# fat-mic-array.net
KiCad netlist of a schematic drawn in EAGLE
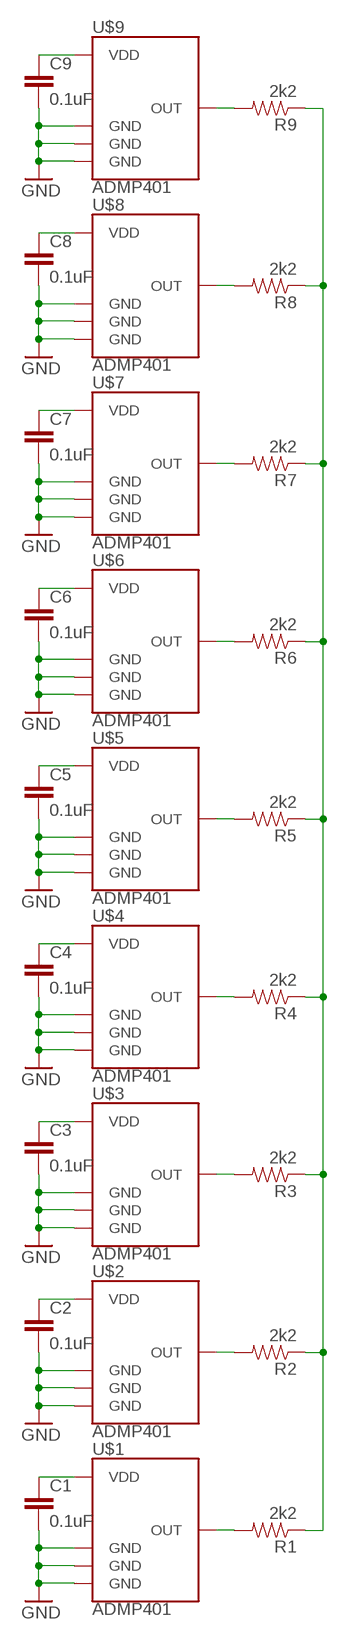
[diagram p0: schematic, sheet 1]

(export (version "E")
  (design (tool "Eeschema 10.0.6"))
  (components
    (comp (ref "C1")
      (value "0.1uF")
      (footprint "eagle-import:0402-CAP")
      (libsource (lib "eagle-import") (part "0.1UF-16V(+-10%)(0402)"))
    )
    (comp (ref "C2")
      (value "0.1uF")
      (footprint "eagle-import:0402-CAP")
      (libsource (lib "eagle-import") (part "0.1UF-16V(+-10%)(0402)"))
    )
    (comp (ref "C3")
      (value "0.1uF")
      (footprint "eagle-import:0402-CAP")
      (libsource (lib "eagle-import") (part "0.1UF-16V(+-10%)(0402)"))
    )
    (comp (ref "C4")
      (value "0.1uF")
      (footprint "eagle-import:0402-CAP")
      (libsource (lib "eagle-import") (part "0.1UF-16V(+-10%)(0402)"))
    )
    (comp (ref "C5")
      (value "0.1uF")
      (footprint "eagle-import:0402-CAP")
      (libsource (lib "eagle-import") (part "0.1UF-16V(+-10%)(0402)"))
    )
    (comp (ref "C6")
      (value "0.1uF")
      (footprint "eagle-import:0402-CAP")
      (libsource (lib "eagle-import") (part "0.1UF-16V(+-10%)(0402)"))
    )
    (comp (ref "C7")
      (value "0.1uF")
      (footprint "eagle-import:0402-CAP")
      (libsource (lib "eagle-import") (part "0.1UF-16V(+-10%)(0402)"))
    )
    (comp (ref "C8")
      (value "0.1uF")
      (footprint "eagle-import:0402-CAP")
      (libsource (lib "eagle-import") (part "0.1UF-16V(+-10%)(0402)"))
    )
    (comp (ref "C9")
      (value "0.1uF")
      (footprint "eagle-import:0402-CAP")
      (libsource (lib "eagle-import") (part "0.1UF-16V(+-10%)(0402)"))
    )
    (comp (ref "R1")
      (value "2k2")
      (footprint "eagle-import:0402-RES")
      (libsource (lib "eagle-import") (part "RESISTOR0402-RES"))
    )
    (comp (ref "R2")
      (value "2k2")
      (footprint "eagle-import:0402-RES")
      (libsource (lib "eagle-import") (part "RESISTOR0402-RES"))
    )
    (comp (ref "R3")
      (value "2k2")
      (footprint "eagle-import:0402-RES")
      (libsource (lib "eagle-import") (part "RESISTOR0402-RES"))
    )
    (comp (ref "R4")
      (value "2k2")
      (footprint "eagle-import:0402-RES")
      (libsource (lib "eagle-import") (part "RESISTOR0402-RES"))
    )
    (comp (ref "R5")
      (value "2k2")
      (footprint "eagle-import:0402-RES")
      (libsource (lib "eagle-import") (part "RESISTOR0402-RES"))
    )
    (comp (ref "R6")
      (value "2k2")
      (footprint "eagle-import:0402-RES")
      (libsource (lib "eagle-import") (part "RESISTOR0402-RES"))
    )
    (comp (ref "R7")
      (value "2k2")
      (footprint "eagle-import:0402-RES")
      (libsource (lib "eagle-import") (part "RESISTOR0402-RES"))
    )
    (comp (ref "R8")
      (value "2k2")
      (footprint "eagle-import:0402-RES")
      (libsource (lib "eagle-import") (part "RESISTOR0402-RES"))
    )
    (comp (ref "R9")
      (value "2k2")
      (footprint "eagle-import:0402-RES")
      (libsource (lib "eagle-import") (part "RESISTOR0402-RES"))
    )
    (comp (ref "U$1")
      (value "ADMP401")
      (footprint "eagle-import:ADMP401")
      (libsource (lib "eagle-import") (part "ADMP401"))
    )
    (comp (ref "U$2")
      (value "ADMP401")
      (footprint "eagle-import:ADMP401")
      (libsource (lib "eagle-import") (part "ADMP401"))
    )
    (comp (ref "U$3")
      (value "ADMP401")
      (footprint "eagle-import:ADMP401")
      (libsource (lib "eagle-import") (part "ADMP401"))
    )
    (comp (ref "U$4")
      (value "ADMP401")
      (footprint "eagle-import:ADMP401")
      (libsource (lib "eagle-import") (part "ADMP401"))
    )
    (comp (ref "U$5")
      (value "ADMP401")
      (footprint "eagle-import:ADMP401")
      (libsource (lib "eagle-import") (part "ADMP401"))
    )
    (comp (ref "U$6")
      (value "ADMP401")
      (footprint "eagle-import:ADMP401")
      (libsource (lib "eagle-import") (part "ADMP401"))
    )
    (comp (ref "U$7")
      (value "ADMP401")
      (footprint "eagle-import:ADMP401")
      (libsource (lib "eagle-import") (part "ADMP401"))
    )
    (comp (ref "U$8")
      (value "ADMP401")
      (footprint "eagle-import:ADMP401")
      (libsource (lib "eagle-import") (part "ADMP401"))
    )
    (comp (ref "U$9")
      (value "ADMP401")
      (footprint "eagle-import:ADMP401")
      (libsource (lib "eagle-import") (part "ADMP401"))
    )
  )
  (nets
    (net (code "1") (name "GND") (class "Default")
      (node (ref "C1") (pin "2") (pinfunction "2_2") (pintype "passive"))
      (node (ref "C2") (pin "2") (pinfunction "2_2") (pintype "passive"))
      (node (ref "C3") (pin "2") (pinfunction "2_2") (pintype "passive"))
      (node (ref "C4") (pin "2") (pinfunction "2_2") (pintype "passive"))
      (node (ref "C5") (pin "2") (pinfunction "2_2") (pintype "passive"))
      (node (ref "C6") (pin "2") (pinfunction "2_2") (pintype "passive"))
      (node (ref "C7") (pin "2") (pinfunction "2_2") (pintype "passive"))
      (node (ref "C8") (pin "2") (pinfunction "2_2") (pintype "passive"))
      (node (ref "C9") (pin "2") (pinfunction "2_2") (pintype "passive"))
      (node (ref "U$1") (pin "2") (pinfunction "GND_2") (pintype "bidirectional"))
      (node (ref "U$1") (pin "4") (pinfunction "GND_4") (pintype "bidirectional"))
      (node (ref "U$1") (pin "6") (pinfunction "GND_6") (pintype "bidirectional"))
      (node (ref "U$2") (pin "2") (pinfunction "GND_2") (pintype "bidirectional"))
      (node (ref "U$2") (pin "4") (pinfunction "GND_4") (pintype "bidirectional"))
      (node (ref "U$2") (pin "6") (pinfunction "GND_6") (pintype "bidirectional"))
      (node (ref "U$3") (pin "2") (pinfunction "GND_2") (pintype "bidirectional"))
      (node (ref "U$3") (pin "4") (pinfunction "GND_4") (pintype "bidirectional"))
      (node (ref "U$3") (pin "6") (pinfunction "GND_6") (pintype "bidirectional"))
      (node (ref "U$4") (pin "2") (pinfunction "GND_2") (pintype "bidirectional"))
      (node (ref "U$4") (pin "4") (pinfunction "GND_4") (pintype "bidirectional"))
      (node (ref "U$4") (pin "6") (pinfunction "GND_6") (pintype "bidirectional"))
      (node (ref "U$5") (pin "2") (pinfunction "GND_2") (pintype "bidirectional"))
      (node (ref "U$5") (pin "4") (pinfunction "GND_4") (pintype "bidirectional"))
      (node (ref "U$5") (pin "6") (pinfunction "GND_6") (pintype "bidirectional"))
      (node (ref "U$6") (pin "2") (pinfunction "GND_2") (pintype "bidirectional"))
      (node (ref "U$6") (pin "4") (pinfunction "GND_4") (pintype "bidirectional"))
      (node (ref "U$6") (pin "6") (pinfunction "GND_6") (pintype "bidirectional"))
      (node (ref "U$7") (pin "2") (pinfunction "GND_2") (pintype "bidirectional"))
      (node (ref "U$7") (pin "4") (pinfunction "GND_4") (pintype "bidirectional"))
      (node (ref "U$7") (pin "6") (pinfunction "GND_6") (pintype "bidirectional"))
      (node (ref "U$8") (pin "2") (pinfunction "GND_2") (pintype "bidirectional"))
      (node (ref "U$8") (pin "4") (pinfunction "GND_4") (pintype "bidirectional"))
      (node (ref "U$8") (pin "6") (pinfunction "GND_6") (pintype "bidirectional"))
      (node (ref "U$9") (pin "2") (pinfunction "GND_2") (pintype "bidirectional"))
      (node (ref "U$9") (pin "4") (pinfunction "GND_4") (pintype "bidirectional"))
      (node (ref "U$9") (pin "6") (pinfunction "GND_6") (pintype "bidirectional"))
    )
    (net (code "2") (name "Net-(R1-Pad1)") (class "Default")
      (node (ref "R1") (pin "1") (pinfunction "1_1") (pintype "passive"))
      (node (ref "R2") (pin "1") (pinfunction "1_1") (pintype "passive"))
      (node (ref "R3") (pin "1") (pinfunction "1_1") (pintype "passive"))
      (node (ref "R4") (pin "1") (pinfunction "1_1") (pintype "passive"))
      (node (ref "R5") (pin "1") (pinfunction "1_1") (pintype "passive"))
      (node (ref "R6") (pin "1") (pinfunction "1_1") (pintype "passive"))
      (node (ref "R7") (pin "1") (pinfunction "1_1") (pintype "passive"))
      (node (ref "R8") (pin "1") (pinfunction "1_1") (pintype "passive"))
      (node (ref "R9") (pin "1") (pinfunction "1_1") (pintype "passive"))
    )
    (net (code "3") (name "Net-(U$1-OUT)") (class "Default")
      (node (ref "R1") (pin "2") (pinfunction "2_2") (pintype "passive"))
      (node (ref "U$1") (pin "1") (pinfunction "OUT_1") (pintype "bidirectional"))
    )
    (net (code "4") (name "Net-(U$1-VDD)") (class "Default")
      (node (ref "C1") (pin "1") (pinfunction "1_1") (pintype "passive"))
      (node (ref "U$1") (pin "5") (pinfunction "VDD_5") (pintype "bidirectional"))
    )
    (net (code "5") (name "Net-(U$2-OUT)") (class "Default")
      (node (ref "R2") (pin "2") (pinfunction "2_2") (pintype "passive"))
      (node (ref "U$2") (pin "1") (pinfunction "OUT_1") (pintype "bidirectional"))
    )
    (net (code "6") (name "Net-(U$2-VDD)") (class "Default")
      (node (ref "C2") (pin "1") (pinfunction "1_1") (pintype "passive"))
      (node (ref "U$2") (pin "5") (pinfunction "VDD_5") (pintype "bidirectional"))
    )
    (net (code "7") (name "Net-(U$3-OUT)") (class "Default")
      (node (ref "R3") (pin "2") (pinfunction "2_2") (pintype "passive"))
      (node (ref "U$3") (pin "1") (pinfunction "OUT_1") (pintype "bidirectional"))
    )
    (net (code "8") (name "Net-(U$3-VDD)") (class "Default")
      (node (ref "C3") (pin "1") (pinfunction "1_1") (pintype "passive"))
      (node (ref "U$3") (pin "5") (pinfunction "VDD_5") (pintype "bidirectional"))
    )
    (net (code "9") (name "Net-(U$4-OUT)") (class "Default")
      (node (ref "R4") (pin "2") (pinfunction "2_2") (pintype "passive"))
      (node (ref "U$4") (pin "1") (pinfunction "OUT_1") (pintype "bidirectional"))
    )
    (net (code "10") (name "Net-(U$4-VDD)") (class "Default")
      (node (ref "C4") (pin "1") (pinfunction "1_1") (pintype "passive"))
      (node (ref "U$4") (pin "5") (pinfunction "VDD_5") (pintype "bidirectional"))
    )
    (net (code "11") (name "Net-(U$5-OUT)") (class "Default")
      (node (ref "R5") (pin "2") (pinfunction "2_2") (pintype "passive"))
      (node (ref "U$5") (pin "1") (pinfunction "OUT_1") (pintype "bidirectional"))
    )
    (net (code "12") (name "Net-(U$5-VDD)") (class "Default")
      (node (ref "C5") (pin "1") (pinfunction "1_1") (pintype "passive"))
      (node (ref "U$5") (pin "5") (pinfunction "VDD_5") (pintype "bidirectional"))
    )
    (net (code "13") (name "Net-(U$6-OUT)") (class "Default")
      (node (ref "R6") (pin "2") (pinfunction "2_2") (pintype "passive"))
      (node (ref "U$6") (pin "1") (pinfunction "OUT_1") (pintype "bidirectional"))
    )
    (net (code "14") (name "Net-(U$6-VDD)") (class "Default")
      (node (ref "C6") (pin "1") (pinfunction "1_1") (pintype "passive"))
      (node (ref "U$6") (pin "5") (pinfunction "VDD_5") (pintype "bidirectional"))
    )
    (net (code "15") (name "Net-(U$7-OUT)") (class "Default")
      (node (ref "R7") (pin "2") (pinfunction "2_2") (pintype "passive"))
      (node (ref "U$7") (pin "1") (pinfunction "OUT_1") (pintype "bidirectional"))
    )
    (net (code "16") (name "Net-(U$7-VDD)") (class "Default")
      (node (ref "C7") (pin "1") (pinfunction "1_1") (pintype "passive"))
      (node (ref "U$7") (pin "5") (pinfunction "VDD_5") (pintype "bidirectional"))
    )
    (net (code "17") (name "Net-(U$8-OUT)") (class "Default")
      (node (ref "R8") (pin "2") (pinfunction "2_2") (pintype "passive"))
      (node (ref "U$8") (pin "1") (pinfunction "OUT_1") (pintype "bidirectional"))
    )
    (net (code "18") (name "Net-(U$8-VDD)") (class "Default")
      (node (ref "C8") (pin "1") (pinfunction "1_1") (pintype "passive"))
      (node (ref "U$8") (pin "5") (pinfunction "VDD_5") (pintype "bidirectional"))
    )
    (net (code "19") (name "Net-(U$9-OUT)") (class "Default")
      (node (ref "R9") (pin "2") (pinfunction "2_2") (pintype "passive"))
      (node (ref "U$9") (pin "1") (pinfunction "OUT_1") (pintype "bidirectional"))
    )
    (net (code "20") (name "Net-(U$9-VDD)") (class "Default")
      (node (ref "C9") (pin "1") (pinfunction "1_1") (pintype "passive"))
      (node (ref "U$9") (pin "5") (pinfunction "VDD_5") (pintype "bidirectional"))
    )
  )
)
